# Thietkehethongnhung.net
KiCad netlist of a schematic drawn in Altium Designer
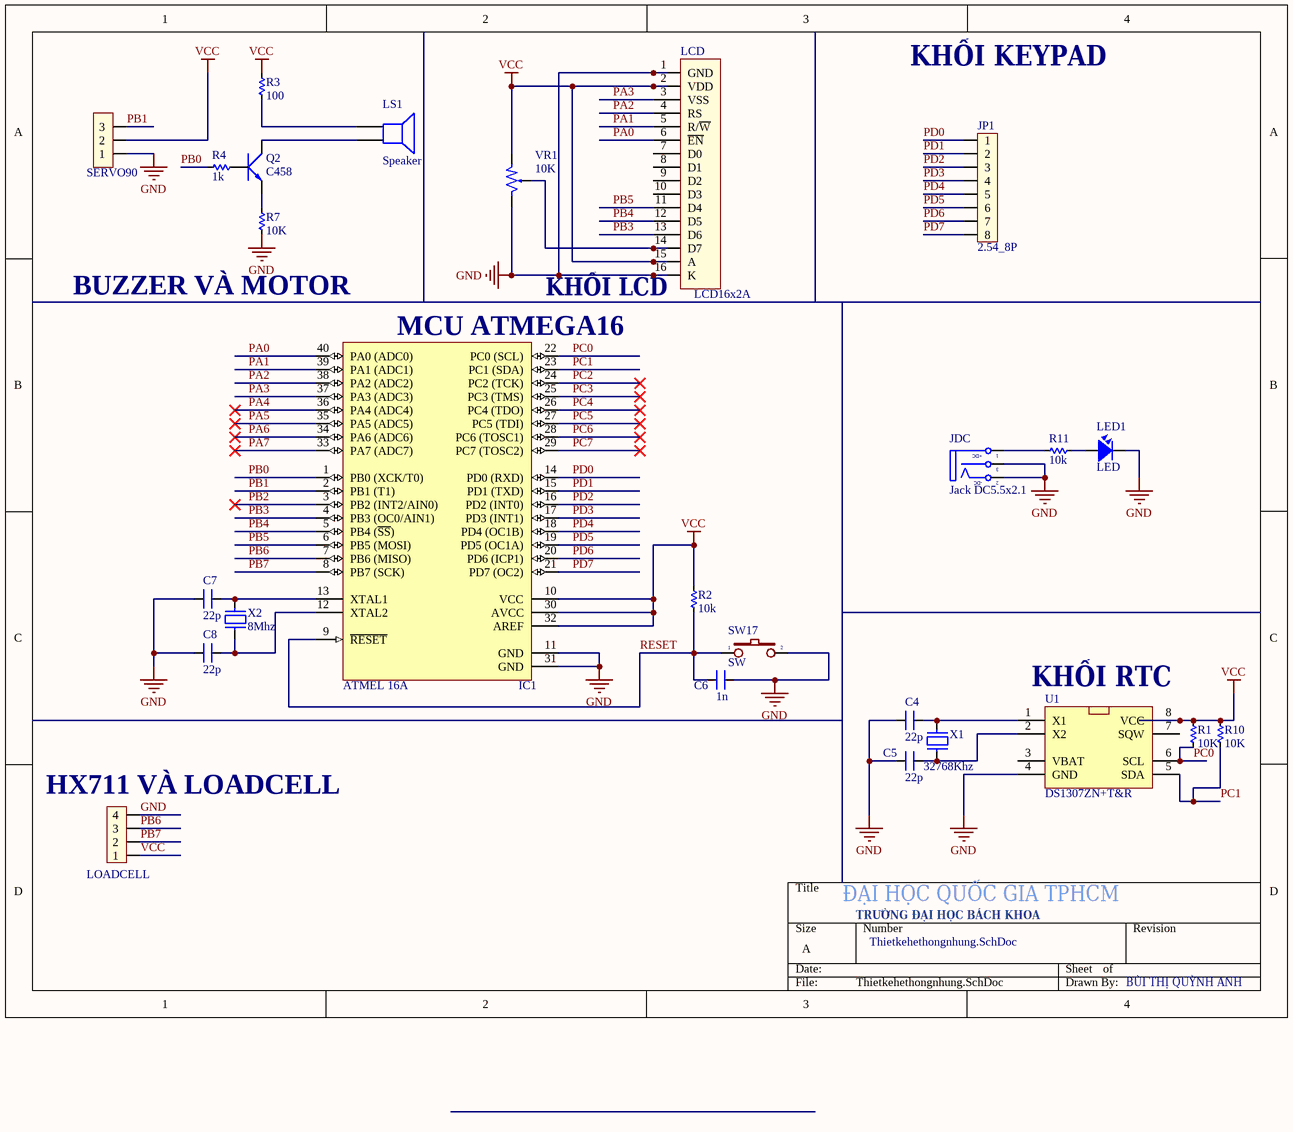
[diagram p0: Thietkehethongnhung.SchDoc]

(export (version "E")
  (design (tool "Eeschema 10.0.6"))
  (components
    (comp (ref "C4")
      (value "22p")
      (footprint "CN1.5")
      (description "Cap np 682pF => 104pF")
      (libsource (lib "KhanhBK_SCH_Library_2") (part "CN1.5"))
    )
    (comp (ref "C5")
      (value "22p")
      (footprint "CN1.5")
      (description "Cap np 682pF => 104pF")
      (libsource (lib "KhanhBK_SCH_Library_2") (part "CN1.5"))
    )
    (comp (ref "C6")
      (value "1n")
      (footprint "CN1.5")
      (description "Cap np 682pF => 104pF")
      (libsource (lib "KhanhBK_SCH_Library_2") (part "CN1.5"))
    )
    (comp (ref "C7")
      (value "22p")
      (footprint "CN1.5")
      (description "Cap np 682pF => 104pF")
      (libsource (lib "KhanhBK_SCH_Library_2") (part "CN1.5"))
    )
    (comp (ref "C8")
      (value "22p")
      (footprint "CN1.5")
      (description "Cap np 682pF => 104pF")
      (libsource (lib "KhanhBK_SCH_Library_2") (part "CN1.5"))
    )
    (comp (ref "IC1")
      (value "ATMEL 16A")
      (footprint "DIP40/W0.6")
      (description "8-Bit AVR Microcontroller with 16K Bytes of In-System Programmable Flash Memory")
      (libsource (lib "KhanhBK_SCH_Library_2") (part "ATmega16A-PU"))
    )
    (comp (ref "J2")
      (value "LOADCELL")
      (footprint "JP4")
      (description "Cắm")
      (libsource (lib "THU VIEN SCH") (part "Jum Don Duc 2.54_4P"))
    )
    (comp (ref "JDC")
      (value "Jack DC5.5x2.1")
      (footprint "DC-IN")
      (description "Cắm")
      (libsource (lib "THU VIEN SCH") (part "Jac_DC"))
    )
    (comp (ref "JP1")
      (value "2.54_8P")
      (footprint "JP8")
      (description "Cắm")
      (libsource (lib "THU VIEN SCH") (part "Jum Don Duc 2.54_8P"))
    )
    (comp (ref "LCD")
      (value "LCD16x2A")
      (footprint "LCD16X2")
      (description "LCD dipslay 16 char, 2 line")
      (libsource (lib "Cty1") (part "LCD16x2"))
    )
    (comp (ref "LED1")
      (value "LED")
      (footprint "LED-3")
      (description "LED Single colour Green and Red")
      (libsource (lib "KhanhBK_SCH_Library_2") (part "LED"))
    )
    (comp (ref "LS1")
      (value "Speaker")
      (footprint "SPEAKER")
      (description "Loudspeaker")
      (fields (field (name "PUBLISHER") "Altium Limited"))
      (libsource (lib "KhanhBK_SCH_Library_2") (part "Speaker"))
    )
    (comp (ref "P1")
      (value "SERVO90")
      (footprint "JP3")
      (description "Cắm")
      (libsource (lib "THU VIEN SCH") (part "Jum Don Duc 2.54_3P"))
    )
    (comp (ref "Q2")
      (value "C458")
      (footprint "TO92-123")
      (description "NPN 600mW, ECB")
      (libsource (lib "KhanhBK_Library_4") (part "C458"))
    )
    (comp (ref "R1")
      (value "10K")
      (footprint "RES-1/2W")
      (description "Res")
      (fields
        (field (name "MANUFACTURER") "Generic Components")
        (field (name "PUBLISHER") "Altium Hobart Technology Centre")
      )
      (libsource (lib "KhanhBK_SCH_Library_1") (part "Res"))
    )
    (comp (ref "R2")
      (value "10k")
      (footprint "RES-1/2W")
      (description "Res")
      (fields
        (field (name "MANUFACTURER") "Generic Components")
        (field (name "PUBLISHER") "Altium Hobart Technology Centre")
      )
      (libsource (lib "KhanhBK_SCH_Library_1") (part "Res"))
    )
    (comp (ref "R3")
      (value "100")
      (footprint "RES-1/2W")
      (description "Res")
      (fields
        (field (name "MANUFACTURER") "Generic Components")
        (field (name "PUBLISHER") "Altium Hobart Technology Centre")
      )
      (libsource (lib "KhanhBK_SCH_Library_1") (part "Res"))
    )
    (comp (ref "R4")
      (value "1k")
      (footprint "RES-1/2W")
      (description "Res")
      (fields
        (field (name "MANUFACTURER") "Generic Components")
        (field (name "PUBLISHER") "Altium Hobart Technology Centre")
      )
      (libsource (lib "KhanhBK_SCH_Library_1") (part "Res"))
    )
    (comp (ref "R7")
      (value "10K")
      (footprint "RES-1/2W")
      (description "Res")
      (fields
        (field (name "MANUFACTURER") "Generic Components")
        (field (name "PUBLISHER") "Altium Hobart Technology Centre")
      )
      (libsource (lib "KhanhBK_SCH_Library_1") (part "Res"))
    )
    (comp (ref "R10")
      (value "10K")
      (footprint "RES-1/2W")
      (description "Res")
      (fields
        (field (name "MANUFACTURER") "Generic Components")
        (field (name "PUBLISHER") "Altium Hobart Technology Centre")
      )
      (libsource (lib "KhanhBK_SCH_Library_1") (part "Res"))
    )
    (comp (ref "R11")
      (value "10k")
      (footprint "RES-1/2W")
      (description "Res")
      (fields
        (field (name "MANUFACTURER") "Generic Components")
        (field (name "PUBLISHER") "Altium Hobart Technology Centre")
      )
      (libsource (lib "KhanhBK_SCH_Library_1") (part "Res"))
    )
    (comp (ref "SW17")
      (value "SW")
      (footprint "SW-RST")
      (description "Switch button 2 pin")
      (libsource (lib "Cty1") (part "SW2"))
    )
    (comp (ref "U1")
      (value "DS1307ZN+T&R")
      (footprint "DIP794W47P254L991H457Q8")
      (description "IC RTC CLK/CALENDAR I2C 8-SOIC")
      (fields (field (name "MANUFACTURER") "Maxim Integrated") (field (name "BASE PART NUMBER") "DS1307"))
      (libsource (lib "KhanhBK_SCH_Lib_6") (part "DS1307ZN+T&R"))
    )
    (comp (ref "VR1")
      (value "10K")
      (footprint "VioletofSun:VR")
      (description "Var Resistor")
      (libsource (lib "VioletofSun") (part "VR1"))
    )
    (comp (ref "X1")
      (value "32768Khz")
      (footprint "XT2")
      (description "Crystal, 32.768 KHz, -40 to 85 degC, 3.2 x 1.5 x 0.9 mm SMD")
      (libsource (lib "KhanhBK_SCH_Library_1") (part "XT2"))
    )
    (comp (ref "X2")
      (value "8Mhz")
      (footprint "XT2")
      (description "Crystal, 32.768 KHz, -40 to 85 degC, 3.2 x 1.5 x 0.9 mm SMD")
      (libsource (lib "KhanhBK_SCH_Library_1") (part "XT2"))
    )
  )
  (nets
    (net (code "1") (name "/PA0") (class "Default")
      (node (ref "IC1") (pin "40") (pinfunction "PA0_(ADC0)_40") (pintype "bidirectional"))
      (node (ref "LCD") (pin "6") (pinfunction "~{EN}_6") (pintype "passive"))
    )
    (net (code "2") (name "/PA1") (class "Default")
      (node (ref "IC1") (pin "39") (pinfunction "PA1_(ADC1)_39") (pintype "bidirectional"))
      (node (ref "LCD") (pin "5") (pinfunction "R/~{W}_5") (pintype "passive"))
    )
    (net (code "3") (name "/PA2") (class "Default")
      (node (ref "IC1") (pin "38") (pinfunction "PA2_(ADC2)_38") (pintype "bidirectional"))
      (node (ref "LCD") (pin "4") (pinfunction "RS_4") (pintype "passive"))
    )
    (net (code "4") (name "/PA3") (class "Default")
      (node (ref "IC1") (pin "37") (pinfunction "PA3_(ADC3)_37") (pintype "bidirectional"))
      (node (ref "LCD") (pin "3") (pinfunction "VSS_3") (pintype "passive"))
    )
    (net (code "5") (name "/PA4") (class "Default")
      (node (ref "IC1") (pin "36") (pinfunction "PA4_(ADC4)_36") (pintype "bidirectional+no_connect"))
    )
    (net (code "6") (name "/PA5") (class "Default")
      (node (ref "IC1") (pin "35") (pinfunction "PA5_(ADC5)_35") (pintype "bidirectional+no_connect"))
    )
    (net (code "7") (name "/PA6") (class "Default")
      (node (ref "IC1") (pin "34") (pinfunction "PA6_(ADC6)_34") (pintype "bidirectional+no_connect"))
    )
    (net (code "8") (name "/PA7") (class "Default")
      (node (ref "IC1") (pin "33") (pinfunction "PA7_(ADC7)_33") (pintype "bidirectional+no_connect"))
    )
    (net (code "9") (name "/PB0") (class "Default")
      (node (ref "IC1") (pin "1") (pinfunction "PB0_(XCK/T0)_1") (pintype "bidirectional"))
      (node (ref "R4") (pin "2") (pinfunction "2_2") (pintype "passive"))
    )
    (net (code "10") (name "/PB1") (class "Default")
      (node (ref "IC1") (pin "2") (pinfunction "PB1_(T1)_2") (pintype "bidirectional"))
      (node (ref "P1") (pin "3") (pinfunction "3_3") (pintype "passive"))
    )
    (net (code "11") (name "/PB2") (class "Default")
      (node (ref "IC1") (pin "3") (pinfunction "PB2_(INT2/AIN0)_3") (pintype "bidirectional+no_connect"))
    )
    (net (code "12") (name "/PB3") (class "Default")
      (node (ref "IC1") (pin "4") (pinfunction "PB3_(OC0/AIN1)_4") (pintype "bidirectional"))
      (node (ref "LCD") (pin "13") (pinfunction "D6_13") (pintype "passive"))
    )
    (net (code "13") (name "/PB4") (class "Default")
      (node (ref "IC1") (pin "5") (pinfunction "PB4_(~{SS})_5") (pintype "bidirectional"))
      (node (ref "LCD") (pin "12") (pinfunction "D5_12") (pintype "passive"))
    )
    (net (code "14") (name "/PB5") (class "Default")
      (node (ref "IC1") (pin "6") (pinfunction "PB5_(MOSI)_6") (pintype "bidirectional"))
      (node (ref "LCD") (pin "11") (pinfunction "D4_11") (pintype "passive"))
    )
    (net (code "15") (name "/PB6") (class "Default")
      (node (ref "IC1") (pin "7") (pinfunction "PB6_(MISO)_7") (pintype "bidirectional"))
      (node (ref "J2") (pin "3") (pinfunction "3_3") (pintype "passive"))
    )
    (net (code "16") (name "/PB7") (class "Default")
      (node (ref "IC1") (pin "8") (pinfunction "PB7_(SCK)_8") (pintype "bidirectional"))
      (node (ref "J2") (pin "2") (pinfunction "2_2") (pintype "passive"))
    )
    (net (code "17") (name "/PC0") (class "Default")
      (node (ref "IC1") (pin "22") (pinfunction "PC0_(SCL)_22") (pintype "bidirectional"))
      (node (ref "R1") (pin "2") (pinfunction "2_2") (pintype "passive"))
      (node (ref "U1") (pin "6") (pinfunction "SCL_6") (pintype "passive"))
    )
    (net (code "18") (name "/PC1") (class "Default")
      (node (ref "IC1") (pin "23") (pinfunction "PC1_(SDA)_23") (pintype "bidirectional"))
      (node (ref "R10") (pin "2") (pinfunction "2_2") (pintype "passive"))
      (node (ref "U1") (pin "5") (pinfunction "SDA_5") (pintype "passive"))
    )
    (net (code "19") (name "/PC2") (class "Default")
      (node (ref "IC1") (pin "24") (pinfunction "PC2_(TCK)_24") (pintype "bidirectional+no_connect"))
    )
    (net (code "20") (name "/PC3") (class "Default")
      (node (ref "IC1") (pin "25") (pinfunction "PC3_(TMS)_25") (pintype "bidirectional+no_connect"))
    )
    (net (code "21") (name "/PC4") (class "Default")
      (node (ref "IC1") (pin "26") (pinfunction "PC4_(TDO)_26") (pintype "bidirectional+no_connect"))
    )
    (net (code "22") (name "/PC5") (class "Default")
      (node (ref "IC1") (pin "27") (pinfunction "PC5_(TDI)_27") (pintype "bidirectional+no_connect"))
    )
    (net (code "23") (name "/PC6") (class "Default")
      (node (ref "IC1") (pin "28") (pinfunction "PC6_(TOSC1)_28") (pintype "bidirectional+no_connect"))
    )
    (net (code "24") (name "/PC7") (class "Default")
      (node (ref "IC1") (pin "29") (pinfunction "PC7_(TOSC2)_29") (pintype "bidirectional+no_connect"))
    )
    (net (code "25") (name "/PD0") (class "Default")
      (node (ref "IC1") (pin "14") (pinfunction "PD0_(RXD)_14") (pintype "bidirectional"))
      (node (ref "JP1") (pin "1") (pinfunction "1_1") (pintype "passive"))
    )
    (net (code "26") (name "/PD1") (class "Default")
      (node (ref "IC1") (pin "15") (pinfunction "PD1_(TXD)_15") (pintype "bidirectional"))
      (node (ref "JP1") (pin "2") (pinfunction "2_2") (pintype "passive"))
    )
    (net (code "27") (name "/PD2") (class "Default")
      (node (ref "IC1") (pin "16") (pinfunction "PD2_(INT0)_16") (pintype "bidirectional"))
      (node (ref "JP1") (pin "3") (pinfunction "3_3") (pintype "passive"))
    )
    (net (code "28") (name "/PD3") (class "Default")
      (node (ref "IC1") (pin "17") (pinfunction "PD3_(INT1)_17") (pintype "bidirectional"))
      (node (ref "JP1") (pin "4") (pinfunction "4_4") (pintype "passive"))
    )
    (net (code "29") (name "/PD4") (class "Default")
      (node (ref "IC1") (pin "18") (pinfunction "PD4_(OC1B)_18") (pintype "bidirectional"))
      (node (ref "JP1") (pin "5") (pinfunction "5_5") (pintype "passive"))
    )
    (net (code "30") (name "/PD5") (class "Default")
      (node (ref "IC1") (pin "19") (pinfunction "PD5_(OC1A)_19") (pintype "bidirectional"))
      (node (ref "JP1") (pin "6") (pinfunction "6_6") (pintype "passive"))
    )
    (net (code "31") (name "/PD6") (class "Default")
      (node (ref "IC1") (pin "20") (pinfunction "PD6_(ICP1)_20") (pintype "bidirectional"))
      (node (ref "JP1") (pin "7") (pinfunction "7_7") (pintype "passive"))
    )
    (net (code "32") (name "/PD7") (class "Default")
      (node (ref "IC1") (pin "21") (pinfunction "PD7_(OC2)_21") (pintype "bidirectional"))
      (node (ref "JP1") (pin "8") (pinfunction "8_8") (pintype "passive"))
    )
    (net (code "33") (name "/RESET") (class "Default")
      (node (ref "C6") (pin "1") (pinfunction "1_1") (pintype "passive"))
      (node (ref "IC1") (pin "9") (pinfunction "~{RESET}_9") (pintype "input"))
      (node (ref "R2") (pin "2") (pinfunction "2_2") (pintype "passive"))
      (node (ref "SW17") (pin "1") (pinfunction "1_1") (pintype "passive"))
    )
    (net (code "34") (name "GND") (class "Default")
      (node (ref "C4") (pin "1") (pinfunction "1_1") (pintype "passive"))
      (node (ref "C5") (pin "1") (pinfunction "1_1") (pintype "passive"))
      (node (ref "C6") (pin "2") (pinfunction "2_2") (pintype "passive"))
      (node (ref "C7") (pin "1") (pinfunction "1_1") (pintype "passive"))
      (node (ref "C8") (pin "1") (pinfunction "1_1") (pintype "passive"))
      (node (ref "IC1") (pin "11") (pinfunction "GND_11") (pintype "power_in"))
      (node (ref "IC1") (pin "31") (pinfunction "GND_31") (pintype "power_in"))
      (node (ref "J2") (pin "4") (pinfunction "4_4") (pintype "passive"))
      (node (ref "JDC") (pin "2") (pinfunction "TN_2") (pintype "passive"))
      (node (ref "JDC") (pin "3") (pinfunction "S_3") (pintype "power_in"))
      (node (ref "LCD") (pin "1") (pinfunction "GND_1") (pintype "passive"))
      (node (ref "LCD") (pin "16") (pinfunction "K_16") (pintype "passive"))
      (node (ref "LED1") (pin "2") (pinfunction "2_2") (pintype "passive"))
      (node (ref "P1") (pin "1") (pinfunction "1_1") (pintype "passive"))
      (node (ref "R7") (pin "2") (pinfunction "2_2") (pintype "passive"))
      (node (ref "SW17") (pin "2") (pinfunction "2_2") (pintype "passive"))
      (node (ref "U1") (pin "4") (pinfunction "GND_4") (pintype "passive"))
      (node (ref "VR1") (pin "3") (pinfunction "3_3") (pintype "passive"))
    )
    (net (code "35") (name "Net-(IC1-XTAL1)") (class "Default")
      (node (ref "C7") (pin "2") (pinfunction "2_2") (pintype "passive"))
      (node (ref "IC1") (pin "13") (pinfunction "XTAL1_13") (pintype "passive"))
      (node (ref "X2") (pin "2") (pinfunction "2_2") (pintype "passive"))
    )
    (net (code "36") (name "Net-(IC1-XTAL2)") (class "Default")
      (node (ref "C8") (pin "2") (pinfunction "2_2") (pintype "passive"))
      (node (ref "IC1") (pin "12") (pinfunction "XTAL2_12") (pintype "passive"))
      (node (ref "X2") (pin "1") (pinfunction "1_1") (pintype "passive"))
    )
    (net (code "37") (name "Net-(JDC-T)") (class "Default")
      (node (ref "JDC") (pin "1") (pinfunction "T_1") (pintype "passive"))
      (node (ref "R11") (pin "1") (pinfunction "1_1") (pintype "passive"))
    )
    (net (code "38") (name "Net-(LCD-D7)") (class "Default")
      (node (ref "LCD") (pin "14") (pinfunction "D7_14") (pintype "passive"))
      (node (ref "VR1") (pin "2") (pinfunction "2_2") (pintype "passive"))
    )
    (net (code "39") (name "Net-(LED1-Pad1)") (class "Default")
      (node (ref "LED1") (pin "1") (pinfunction "1_1") (pintype "passive"))
      (node (ref "R11") (pin "2") (pinfunction "2_2") (pintype "passive"))
    )
    (net (code "40") (name "Net-(LS1-Pad1)") (class "Default")
      (node (ref "LS1") (pin "1") (pinfunction "1_1") (pintype "passive"))
      (node (ref "R3") (pin "1") (pinfunction "1_1") (pintype "passive"))
    )
    (net (code "41") (name "Net-(Q2-B)") (class "Default")
      (node (ref "Q2") (pin "3") (pinfunction "B_3") (pintype "passive"))
      (node (ref "R4") (pin "1") (pinfunction "1_1") (pintype "passive"))
    )
    (net (code "42") (name "Net-(Q2-C)") (class "Default")
      (node (ref "LS1") (pin "2") (pinfunction "2_2") (pintype "passive"))
      (node (ref "Q2") (pin "2") (pinfunction "C_2") (pintype "passive"))
    )
    (net (code "43") (name "Net-(Q2-E)") (class "Default")
      (node (ref "Q2") (pin "1") (pinfunction "E_1") (pintype "passive"))
      (node (ref "R7") (pin "1") (pinfunction "1_1") (pintype "passive"))
    )
    (net (code "44") (name "Net-(U1-X1)") (class "Default")
      (node (ref "C4") (pin "2") (pinfunction "2_2") (pintype "passive"))
      (node (ref "U1") (pin "1") (pinfunction "X1_1") (pintype "passive"))
      (node (ref "X1") (pin "2") (pinfunction "2_2") (pintype "passive"))
    )
    (net (code "45") (name "Net-(U1-X2)") (class "Default")
      (node (ref "C5") (pin "2") (pinfunction "2_2") (pintype "passive"))
      (node (ref "U1") (pin "2") (pinfunction "X2_2") (pintype "passive"))
      (node (ref "X1") (pin "1") (pinfunction "1_1") (pintype "passive"))
    )
    (net (code "46") (name "VCC") (class "Default")
      (node (ref "IC1") (pin "10") (pinfunction "VCC_10") (pintype "power_in"))
      (node (ref "IC1") (pin "30") (pinfunction "AVCC_30") (pintype "power_in"))
      (node (ref "IC1") (pin "32") (pinfunction "AREF_32") (pintype "power_in"))
      (node (ref "J2") (pin "1") (pinfunction "1_1") (pintype "passive"))
      (node (ref "LCD") (pin "15") (pinfunction "A_15") (pintype "passive"))
      (node (ref "LCD") (pin "2") (pinfunction "VDD_2") (pintype "passive"))
      (node (ref "P1") (pin "2") (pinfunction "2_2") (pintype "passive"))
      (node (ref "R1") (pin "1") (pinfunction "1_1") (pintype "passive"))
      (node (ref "R10") (pin "1") (pinfunction "1_1") (pintype "passive"))
      (node (ref "R2") (pin "1") (pinfunction "1_1") (pintype "passive"))
      (node (ref "R3") (pin "2") (pinfunction "2_2") (pintype "passive"))
      (node (ref "U1") (pin "8") (pinfunction "VCC_8") (pintype "passive"))
      (node (ref "VR1") (pin "1") (pinfunction "1_1") (pintype "passive"))
    )
    (net (code "47") (name "unconnected-(LCD-D0-Pad7)") (class "Default")
      (node (ref "LCD") (pin "7") (pinfunction "D0_7") (pintype "passive"))
    )
    (net (code "48") (name "unconnected-(LCD-D1-Pad8)") (class "Default")
      (node (ref "LCD") (pin "8") (pinfunction "D1_8") (pintype "passive"))
    )
    (net (code "49") (name "unconnected-(LCD-D2-Pad9)") (class "Default")
      (node (ref "LCD") (pin "9") (pinfunction "D2_9") (pintype "passive"))
    )
    (net (code "50") (name "unconnected-(LCD-D3-Pad10)") (class "Default")
      (node (ref "LCD") (pin "10") (pinfunction "D3_10") (pintype "passive"))
    )
    (net (code "51") (name "unconnected-(U1-SQW-Pad7)") (class "Default")
      (node (ref "U1") (pin "7") (pinfunction "SQW_7") (pintype "passive"))
    )
    (net (code "52") (name "unconnected-(U1-VBAT-Pad3)") (class "Default")
      (node (ref "U1") (pin "3") (pinfunction "VBAT_3") (pintype "passive"))
    )
  )
)
